# LinuxBoard_v1_1.net
KiCad netlist of a schematic drawn in EAGLE
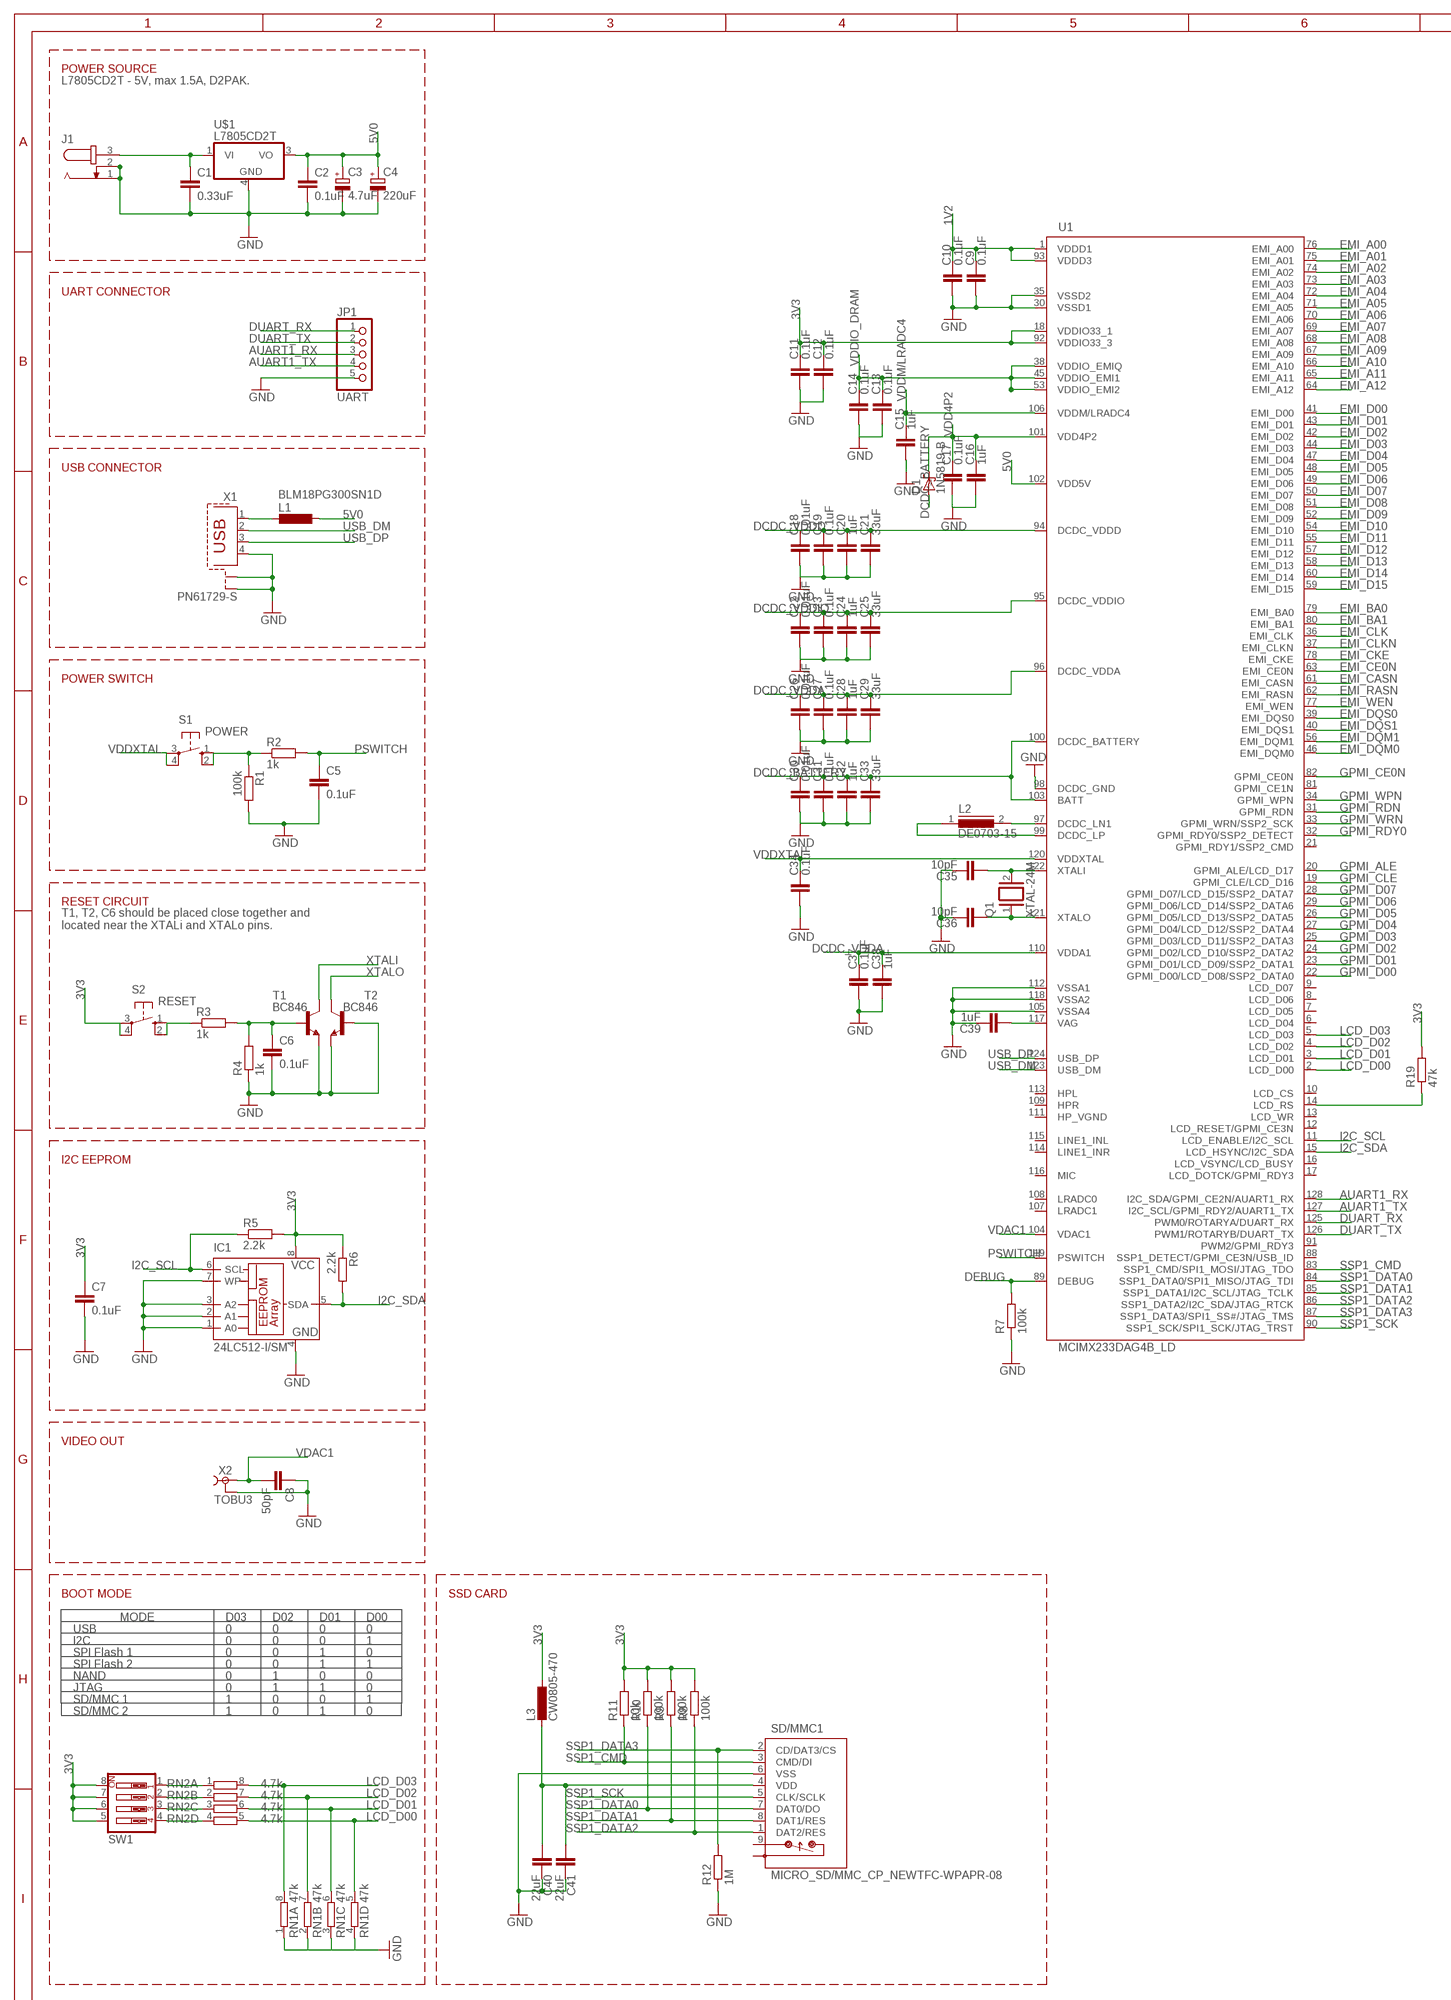
[diagram p0: schematic, sheet 1, part 1 of 2]
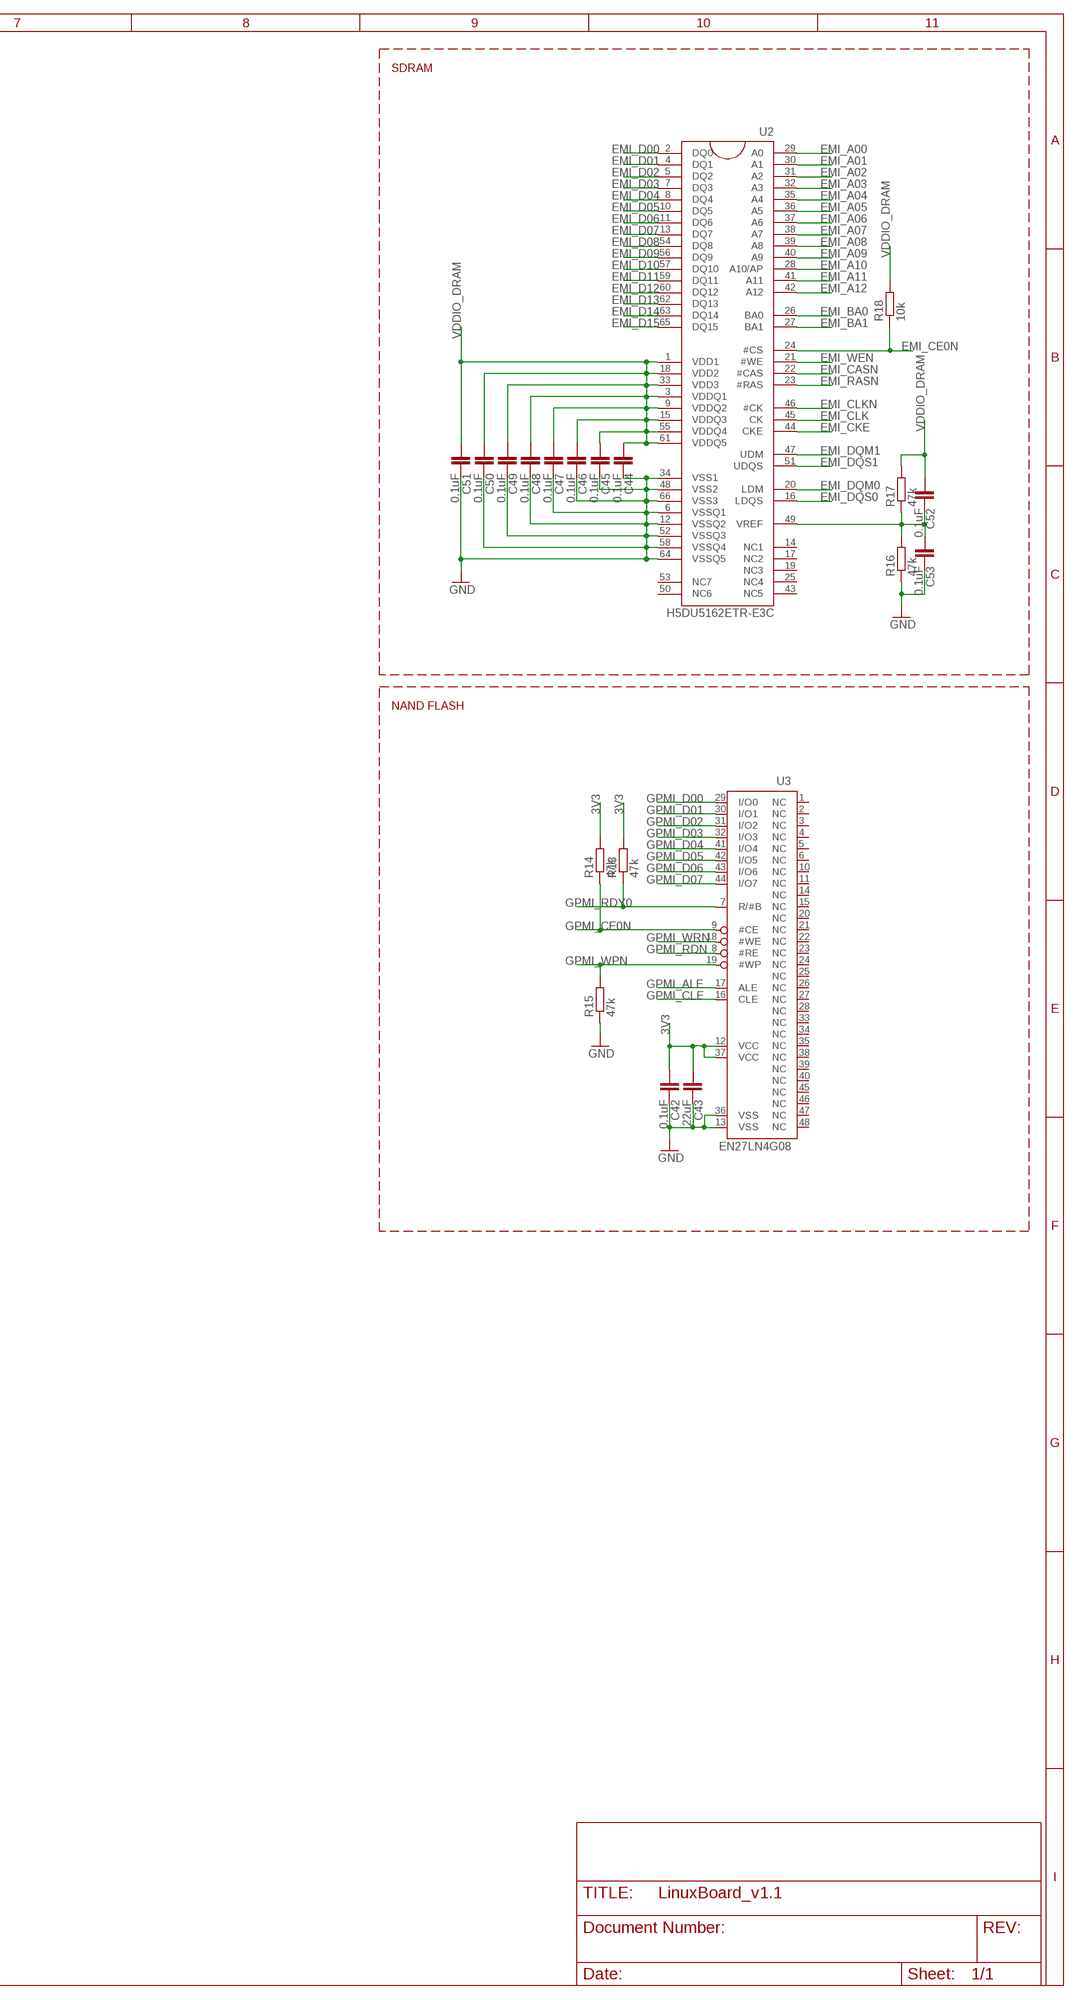
[diagram p1: schematic, sheet 1, part 2 of 2]

(export (version "E")
  (design (tool "Eeschema 10.0.6"))
  (components
    (comp (ref "C1")
      (value "0.33uF")
      (footprint "eagle-import:C0805")
      (libsource (lib "eagle-import") (part "C-EUC0805"))
    )
    (comp (ref "C2")
      (value "0.1uF")
      (footprint "eagle-import:C0805")
      (libsource (lib "eagle-import") (part "C-EUC0805"))
    )
    (comp (ref "C3")
      (value "4.7uF")
      (footprint "eagle-import:E2-5")
      (libsource (lib "eagle-import") (part "CPOL-EUE2-5"))
    )
    (comp (ref "C4")
      (value "220uF")
      (footprint "eagle-import:E2-5")
      (libsource (lib "eagle-import") (part "CPOL-EUE2-5"))
    )
    (comp (ref "C5")
      (value "0.1uF")
      (footprint "eagle-import:C0805")
      (libsource (lib "eagle-import") (part "C-EUC0805"))
    )
    (comp (ref "C6")
      (value "0.1uF")
      (footprint "eagle-import:C0805")
      (libsource (lib "eagle-import") (part "C-EUC0805"))
    )
    (comp (ref "C7")
      (value "0.1uF")
      (footprint "eagle-import:C0805")
      (libsource (lib "eagle-import") (part "C-EUC0805"))
    )
    (comp (ref "C8")
      (value "50pF")
      (footprint "eagle-import:C0805")
      (libsource (lib "eagle-import") (part "C-EUC0805"))
    )
    (comp (ref "C9")
      (value "0.1uF")
      (footprint "eagle-import:C0805")
      (libsource (lib "eagle-import") (part "C-EUC0805"))
    )
    (comp (ref "C10")
      (value "0.1uF")
      (footprint "eagle-import:C0805")
      (libsource (lib "eagle-import") (part "C-EUC0805"))
    )
    (comp (ref "C11")
      (value "0.1uF")
      (footprint "eagle-import:C0805")
      (libsource (lib "eagle-import") (part "C-EUC0805"))
    )
    (comp (ref "C12")
      (value "0.1uF")
      (footprint "eagle-import:C0805")
      (libsource (lib "eagle-import") (part "C-EUC0805"))
    )
    (comp (ref "C13")
      (value "0.1uF")
      (footprint "eagle-import:C0805")
      (libsource (lib "eagle-import") (part "C-EUC0805"))
    )
    (comp (ref "C14")
      (value "0.1uF")
      (footprint "eagle-import:C0805")
      (libsource (lib "eagle-import") (part "C-EUC0805"))
    )
    (comp (ref "C15")
      (value "1uF")
      (footprint "eagle-import:C0805")
      (libsource (lib "eagle-import") (part "C-EUC0805"))
    )
    (comp (ref "C16")
      (value "1uF")
      (footprint "eagle-import:C0805")
      (libsource (lib "eagle-import") (part "C-EUC0805"))
    )
    (comp (ref "C17")
      (value "0.1uF")
      (footprint "eagle-import:C0805")
      (libsource (lib "eagle-import") (part "C-EUC0805"))
    )
    (comp (ref "C18")
      (value "0.01uF")
      (footprint "eagle-import:C0805")
      (libsource (lib "eagle-import") (part "C-EUC0805"))
    )
    (comp (ref "C19")
      (value "0.1uF")
      (footprint "eagle-import:C0805")
      (libsource (lib "eagle-import") (part "C-EUC0805"))
    )
    (comp (ref "C20")
      (value "1uF")
      (footprint "eagle-import:C0805")
      (libsource (lib "eagle-import") (part "C-EUC0805"))
    )
    (comp (ref "C21")
      (value "33uF")
      (footprint "eagle-import:C0805")
      (libsource (lib "eagle-import") (part "C-EUC0805"))
    )
    (comp (ref "C22")
      (value "0.01uF")
      (footprint "eagle-import:C0805")
      (libsource (lib "eagle-import") (part "C-EUC0805"))
    )
    (comp (ref "C23")
      (value "0.1uF")
      (footprint "eagle-import:C0805")
      (libsource (lib "eagle-import") (part "C-EUC0805"))
    )
    (comp (ref "C24")
      (value "1uF")
      (footprint "eagle-import:C0805")
      (libsource (lib "eagle-import") (part "C-EUC0805"))
    )
    (comp (ref "C25")
      (value "33uF")
      (footprint "eagle-import:C0805")
      (libsource (lib "eagle-import") (part "C-EUC0805"))
    )
    (comp (ref "C26")
      (value "0.01uF")
      (footprint "eagle-import:C0805")
      (libsource (lib "eagle-import") (part "C-EUC0805"))
    )
    (comp (ref "C27")
      (value "0.1uF")
      (footprint "eagle-import:C0805")
      (libsource (lib "eagle-import") (part "C-EUC0805"))
    )
    (comp (ref "C28")
      (value "1uF")
      (footprint "eagle-import:C0805")
      (libsource (lib "eagle-import") (part "C-EUC0805"))
    )
    (comp (ref "C29")
      (value "33uF")
      (footprint "eagle-import:C0805")
      (libsource (lib "eagle-import") (part "C-EUC0805"))
    )
    (comp (ref "C30")
      (value "0.01uF")
      (footprint "eagle-import:C0805")
      (libsource (lib "eagle-import") (part "C-EUC0805"))
    )
    (comp (ref "C31")
      (value "0.1uF")
      (footprint "eagle-import:C0805")
      (libsource (lib "eagle-import") (part "C-EUC0805"))
    )
    (comp (ref "C32")
      (value "1uF")
      (footprint "eagle-import:C0805")
      (libsource (lib "eagle-import") (part "C-EUC0805"))
    )
    (comp (ref "C33")
      (value "33uF")
      (footprint "eagle-import:C0805")
      (libsource (lib "eagle-import") (part "C-EUC0805"))
    )
    (comp (ref "C34")
      (value "0.1uF")
      (footprint "eagle-import:C0805")
      (libsource (lib "eagle-import") (part "C-EUC0805"))
    )
    (comp (ref "C35")
      (value "10pF")
      (footprint "eagle-import:C0805")
      (libsource (lib "eagle-import") (part "C-EUC0805"))
    )
    (comp (ref "C36")
      (value "10pF")
      (footprint "eagle-import:C0805")
      (libsource (lib "eagle-import") (part "C-EUC0805"))
    )
    (comp (ref "C37")
      (value "0.1uF")
      (footprint "eagle-import:C0805")
      (libsource (lib "eagle-import") (part "C-EUC0805"))
    )
    (comp (ref "C38")
      (value "1uF")
      (footprint "eagle-import:C0805")
      (libsource (lib "eagle-import") (part "C-EUC0805"))
    )
    (comp (ref "C39")
      (value "1uF")
      (footprint "eagle-import:C0805")
      (libsource (lib "eagle-import") (part "C-EUC0805"))
    )
    (comp (ref "C40")
      (value "22uF")
      (footprint "eagle-import:C0805")
      (libsource (lib "eagle-import") (part "C-EUC0805"))
    )
    (comp (ref "C41")
      (value "22uF")
      (footprint "eagle-import:C0805")
      (libsource (lib "eagle-import") (part "C-EUC0805"))
    )
    (comp (ref "C42")
      (value "0.1uF")
      (footprint "eagle-import:C0805")
      (libsource (lib "eagle-import") (part "C-EUC0805"))
    )
    (comp (ref "C43")
      (value "22uF")
      (footprint "eagle-import:C0805")
      (libsource (lib "eagle-import") (part "C-EUC0805"))
    )
    (comp (ref "C44")
      (value "0.1uF")
      (footprint "eagle-import:C0805")
      (libsource (lib "eagle-import") (part "C-EUC0805"))
    )
    (comp (ref "C45")
      (value "0.1uF")
      (footprint "eagle-import:C0805")
      (libsource (lib "eagle-import") (part "C-EUC0805"))
    )
    (comp (ref "C46")
      (value "0.1uF")
      (footprint "eagle-import:C0805")
      (libsource (lib "eagle-import") (part "C-EUC0805"))
    )
    (comp (ref "C47")
      (value "0.1uF")
      (footprint "eagle-import:C0805")
      (libsource (lib "eagle-import") (part "C-EUC0805"))
    )
    (comp (ref "C48")
      (value "0.1uF")
      (footprint "eagle-import:C0805")
      (libsource (lib "eagle-import") (part "C-EUC0805"))
    )
    (comp (ref "C49")
      (value "0.1uF")
      (footprint "eagle-import:C0805")
      (libsource (lib "eagle-import") (part "C-EUC0805"))
    )
    (comp (ref "C50")
      (value "0.1uF")
      (footprint "eagle-import:C0805")
      (libsource (lib "eagle-import") (part "C-EUC0805"))
    )
    (comp (ref "C51")
      (value "0.1uF")
      (footprint "eagle-import:C0805")
      (libsource (lib "eagle-import") (part "C-EUC0805"))
    )
    (comp (ref "C52")
      (value "0.1uF")
      (footprint "eagle-import:C0805")
      (libsource (lib "eagle-import") (part "C-EUC0805"))
    )
    (comp (ref "C53")
      (value "0.1uF")
      (footprint "eagle-import:C0805")
      (libsource (lib "eagle-import") (part "C-EUC0805"))
    )
    (comp (ref "D1")
      (value "1N5819-B")
      (footprint "eagle-import:DO41-7.6")
      (libsource (lib "eagle-import") (part "1N5819-B"))
    )
    (comp (ref "IC1")
      (value "24LC512-I/SM")
      (footprint "eagle-import:SO-08")
      (fields (field (name "MF") "MICROCHIP") (field (name "MPN") "24LC128-I/SNG"))
      (libsource (lib "eagle-import") (part "24SNLC128"))
    )
    (comp (ref "J1")
      (value "JACK-PLUG0")
      (footprint "eagle-import:SPC4077")
      (libsource (lib "eagle-import") (part "JACK-PLUG0"))
    )
    (comp (ref "JP1")
      (value "UART")
      (footprint "eagle-import:1X05")
      (libsource (lib "eagle-import") (part "PINHD-1X5"))
    )
    (comp (ref "L1")
      (value "BLM18PG300SN1D")
      (footprint "eagle-import:L0201")
      (libsource (lib "eagle-import") (part "L-EUL0201"))
    )
    (comp (ref "L2")
      (value "DE0703-15")
      (footprint "eagle-import:DR73")
      (libsource (lib "eagle-import") (part "DR73"))
    )
    (comp (ref "L3")
      (value "CW0805-470")
      (footprint "eagle-import:L2012C")
      (libsource (lib "eagle-import") (part "L-EUL2012C"))
    )
    (comp (ref "Q1")
      (value "XTAL-24M")
      (footprint "eagle-import:QS")
      (libsource (lib "eagle-import") (part "XTAL/S"))
    )
    (comp (ref "R1")
      (value "100k")
      (footprint "eagle-import:R0805")
      (libsource (lib "eagle-import") (part "R-EU_R0805"))
    )
    (comp (ref "R2")
      (value "1k")
      (footprint "eagle-import:R0805")
      (libsource (lib "eagle-import") (part "R-EU_R0805"))
    )
    (comp (ref "R3")
      (value "1k")
      (footprint "eagle-import:R0805")
      (libsource (lib "eagle-import") (part "R-EU_R0805"))
    )
    (comp (ref "R4")
      (value "1k")
      (footprint "eagle-import:R0805")
      (libsource (lib "eagle-import") (part "R-EU_R0805"))
    )
    (comp (ref "R5")
      (value "2.2k")
      (footprint "eagle-import:R0805")
      (libsource (lib "eagle-import") (part "R-EU_R0805"))
    )
    (comp (ref "R6")
      (value "2.2k")
      (footprint "eagle-import:R0805")
      (libsource (lib "eagle-import") (part "R-EU_R0805"))
    )
    (comp (ref "R7")
      (value "100k")
      (footprint "eagle-import:R0805")
      (libsource (lib "eagle-import") (part "R-EU_R0805"))
    )
    (comp (ref "R8")
      (value "100k")
      (footprint "eagle-import:R0805")
      (libsource (lib "eagle-import") (part "R-EU_R0805"))
    )
    (comp (ref "R9")
      (value "100k")
      (footprint "eagle-import:R0805")
      (libsource (lib "eagle-import") (part "R-EU_R0805"))
    )
    (comp (ref "R10")
      (value "100k")
      (footprint "eagle-import:R0805")
      (libsource (lib "eagle-import") (part "R-EU_R0805"))
    )
    (comp (ref "R11")
      (value "10k")
      (footprint "eagle-import:R0805")
      (libsource (lib "eagle-import") (part "R-EU_R0805"))
    )
    (comp (ref "R12")
      (value "1M")
      (footprint "eagle-import:R0805")
      (libsource (lib "eagle-import") (part "R-EU_R0805"))
    )
    (comp (ref "R13")
      (value "47k")
      (footprint "eagle-import:R0805")
      (libsource (lib "eagle-import") (part "R-EU_R0805"))
    )
    (comp (ref "R14")
      (value "47k")
      (footprint "eagle-import:R0805")
      (libsource (lib "eagle-import") (part "R-EU_R0805"))
    )
    (comp (ref "R15")
      (value "47k")
      (footprint "eagle-import:R0805")
      (libsource (lib "eagle-import") (part "R-EU_R0805"))
    )
    (comp (ref "R16")
      (value "47k")
      (footprint "eagle-import:R0805")
      (libsource (lib "eagle-import") (part "R-EU_R0805"))
    )
    (comp (ref "R17")
      (value "47k")
      (footprint "eagle-import:R0805")
      (libsource (lib "eagle-import") (part "R-EU_R0805"))
    )
    (comp (ref "R18")
      (value "10k")
      (footprint "eagle-import:R0805")
      (libsource (lib "eagle-import") (part "R-EU_R0805"))
    )
    (comp (ref "R19")
      (value "47k")
      (footprint "eagle-import:R0805")
      (libsource (lib "eagle-import") (part "R-EU_R0805"))
    )
    (comp (ref "RN1")
      (value "47k")
      (footprint "eagle-import:YC124")
      (libsource (lib "eagle-import") (part "4R-NYC124"))
    )
    (comp (ref "RN2")
      (value "4.7k")
      (footprint "eagle-import:YC124")
      (libsource (lib "eagle-import") (part "4R-NYC124"))
    )
    (comp (ref "S1")
      (value "POWER")
      (footprint "eagle-import:B3F-10XX")
      (fields (field (name "MPN") "B3F-1000"))
      (libsource (lib "eagle-import") (part "10-XX"))
    )
    (comp (ref "S2")
      (value "RESET")
      (footprint "eagle-import:B3F-10XX")
      (fields (field (name "MPN") "B3F-1000"))
      (libsource (lib "eagle-import") (part "10-XX"))
    )
    (comp (ref "SD/MMC1")
      (value "MICRO_SD/MMC_CP_NEWTFC-WPAPR-08")
      (footprint "eagle-import:TFC-WPAPR-08")
      (libsource (lib "eagle-import") (part "MICRO_SD/MMC_CP_NEWTFC-WPAPR-08"))
    )
    (comp (ref "SW1")
      (value "SW_DIP-4")
      (footprint "eagle-import:EDG-04")
      (libsource (lib "eagle-import") (part "SW_DIP-4"))
    )
    (comp (ref "T1")
      (value "BC846")
      (footprint "eagle-import:SOT23")
      (libsource (lib "eagle-import") (part "BC846"))
    )
    (comp (ref "T2")
      (value "BC846")
      (footprint "eagle-import:SOT23")
      (libsource (lib "eagle-import") (part "BC846"))
    )
    (comp (ref "U$1")
      (value "L7805CD2T")
      (footprint "eagle-import:D2PAK-3")
      (libsource (lib "eagle-import") (part "L7805CD2T"))
    )
    (comp (ref "U1")
      (value "MCIMX233DAG4B_LD")
      (footprint "eagle-import:TQFP128LD")
      (libsource (lib "eagle-import") (part "MCIMX233DAG4B_LD"))
    )
    (comp (ref "U2")
      (value "H5DU5162ETR-E3C")
      (footprint "eagle-import:66TSOP-II")
      (libsource (lib "eagle-import") (part "HY5DU121622D(L)T(P)-J"))
    )
    (comp (ref "U3")
      (value "EN27LN4G08")
      (footprint "eagle-import:TSOP48")
      (libsource (lib "eagle-import") (part "H27UBG8T2A"))
    )
    (comp (ref "X1")
      (value "PN61729-S")
      (footprint "eagle-import:PN61729-S")
      (libsource (lib "eagle-import") (part "PN61729-S"))
    )
    (comp (ref "X2")
      (value "TOBU3")
      (footprint "eagle-import:TOBU3")
      (fields (field (name "MF") "FARNELL") (field (name "MPN") "TOBU 3"))
      (libsource (lib "eagle-import") (part "TOBU3"))
    )
  )
  (nets
    (net (code "1") (name "/1V2") (class "Default")
      (node (ref "C10") (pin "1") (pinfunction "1_1") (pintype "passive"))
      (node (ref "C9") (pin "1") (pinfunction "1_1") (pintype "passive"))
      (node (ref "U1") (pin "1") (pinfunction "VDDD1_1") (pintype "power_in"))
      (node (ref "U1") (pin "93") (pinfunction "VDDD3_93") (pintype "power_in"))
    )
    (net (code "2") (name "/3V3") (class "Default")
      (node (ref "C11") (pin "1") (pinfunction "1_1") (pintype "passive"))
      (node (ref "C12") (pin "1") (pinfunction "1_1") (pintype "passive"))
      (node (ref "C42") (pin "2") (pinfunction "2_2") (pintype "passive"))
      (node (ref "C43") (pin "2") (pinfunction "2_2") (pintype "passive"))
      (node (ref "C7") (pin "1") (pinfunction "1_1") (pintype "passive"))
      (node (ref "IC1") (pin "8") (pinfunction "VCC_8") (pintype "power_in"))
      (node (ref "L3") (pin "1") (pinfunction "1_1") (pintype "passive"))
      (node (ref "R10") (pin "2") (pinfunction "2_2") (pintype "passive"))
      (node (ref "R11") (pin "2") (pinfunction "2_2") (pintype "passive"))
      (node (ref "R13") (pin "2") (pinfunction "2_2") (pintype "passive"))
      (node (ref "R14") (pin "2") (pinfunction "2_2") (pintype "passive"))
      (node (ref "R19") (pin "2") (pinfunction "2_2") (pintype "passive"))
      (node (ref "R5") (pin "2") (pinfunction "2_2") (pintype "passive"))
      (node (ref "R6") (pin "1") (pinfunction "1_1") (pintype "passive"))
      (node (ref "R8") (pin "2") (pinfunction "2_2") (pintype "passive"))
      (node (ref "R9") (pin "2") (pinfunction "2_2") (pintype "passive"))
      (node (ref "S2") (pin "3") (pinfunction "P_3") (pintype "passive"))
      (node (ref "S2") (pin "4") (pinfunction "P1_4") (pintype "passive"))
      (node (ref "SW1") (pin "5") (pinfunction "5_5") (pintype "passive"))
      (node (ref "SW1") (pin "6") (pinfunction "6_6") (pintype "passive"))
      (node (ref "SW1") (pin "7") (pinfunction "7_7") (pintype "passive"))
      (node (ref "SW1") (pin "8") (pinfunction "8_8") (pintype "passive"))
      (node (ref "U1") (pin "18") (pinfunction "VDDIO33_1_18") (pintype "power_in"))
      (node (ref "U1") (pin "92") (pinfunction "VDDIO33_3_92") (pintype "power_in"))
      (node (ref "U3") (pin "12") (pinfunction "VCC_12") (pintype "power_in"))
      (node (ref "U3") (pin "37") (pinfunction "VCC_37") (pintype "power_in"))
    )
    (net (code "3") (name "/5V0") (class "Default")
      (node (ref "C2") (pin "1") (pinfunction "1_1") (pintype "passive"))
      (node (ref "C3") (pin "+") (pinfunction "+_+") (pintype "passive"))
      (node (ref "C4") (pin "+") (pinfunction "+_+") (pintype "passive"))
      (node (ref "L1") (pin "1") (pinfunction "1_1") (pintype "passive"))
      (node (ref "U$1") (pin "3") (pinfunction "VO_3") (pintype "passive"))
      (node (ref "U1") (pin "102") (pinfunction "VDD5V_102") (pintype "power_in"))
    )
    (net (code "4") (name "/AUART1_RX") (class "Default")
      (node (ref "JP1") (pin "3") (pinfunction "3_3") (pintype "passive"))
      (node (ref "U1") (pin "128") (pinfunction "I2C_SDA/GPMI_CE2N/AUART1_RX_128") (pintype "bidirectional"))
    )
    (net (code "5") (name "/AUART1_TX") (class "Default")
      (node (ref "JP1") (pin "4") (pinfunction "4_4") (pintype "passive"))
      (node (ref "U1") (pin "127") (pinfunction "I2C_SCL/GPMI_RDY2/AUART1_TX_127") (pintype "bidirectional"))
    )
    (net (code "6") (name "/DCDC_BATTERY") (class "Default")
      (node (ref "C30") (pin "1") (pinfunction "1_1") (pintype "passive"))
      (node (ref "C31") (pin "1") (pinfunction "1_1") (pintype "passive"))
      (node (ref "C32") (pin "1") (pinfunction "1_1") (pintype "passive"))
      (node (ref "C33") (pin "1") (pinfunction "1_1") (pintype "passive"))
      (node (ref "D1") (pin "A") (pinfunction "A_A") (pintype "passive"))
      (node (ref "U1") (pin "100") (pinfunction "DCDC_BATTERY_100") (pintype "power_in"))
      (node (ref "U1") (pin "103") (pinfunction "BATT_103") (pintype "input"))
    )
    (net (code "7") (name "/DCDC_VDDA") (class "Default")
      (node (ref "C26") (pin "1") (pinfunction "1_1") (pintype "passive"))
      (node (ref "C27") (pin "1") (pinfunction "1_1") (pintype "passive"))
      (node (ref "C28") (pin "1") (pinfunction "1_1") (pintype "passive"))
      (node (ref "C29") (pin "1") (pinfunction "1_1") (pintype "passive"))
      (node (ref "C37") (pin "1") (pinfunction "1_1") (pintype "passive"))
      (node (ref "C38") (pin "1") (pinfunction "1_1") (pintype "passive"))
      (node (ref "U1") (pin "110") (pinfunction "VDDA1_110") (pintype "power_in"))
      (node (ref "U1") (pin "96") (pinfunction "DCDC_VDDA_96") (pintype "power_in"))
    )
    (net (code "8") (name "/DCDC_VDDD") (class "Default")
      (node (ref "C18") (pin "1") (pinfunction "1_1") (pintype "passive"))
      (node (ref "C19") (pin "1") (pinfunction "1_1") (pintype "passive"))
      (node (ref "C20") (pin "1") (pinfunction "1_1") (pintype "passive"))
      (node (ref "C21") (pin "1") (pinfunction "1_1") (pintype "passive"))
      (node (ref "U1") (pin "94") (pinfunction "DCDC_VDDD_94") (pintype "power_in"))
    )
    (net (code "9") (name "/DCDC_VDDIO") (class "Default")
      (node (ref "C22") (pin "1") (pinfunction "1_1") (pintype "passive"))
      (node (ref "C23") (pin "1") (pinfunction "1_1") (pintype "passive"))
      (node (ref "C24") (pin "1") (pinfunction "1_1") (pintype "passive"))
      (node (ref "C25") (pin "1") (pinfunction "1_1") (pintype "passive"))
      (node (ref "U1") (pin "95") (pinfunction "DCDC_VDDIO_95") (pintype "power_in"))
    )
    (net (code "10") (name "/DEBUG") (class "Default")
      (node (ref "R7") (pin "2") (pinfunction "2_2") (pintype "passive"))
      (node (ref "U1") (pin "89") (pinfunction "DEBUG_89") (pintype "bidirectional"))
    )
    (net (code "11") (name "/DUART_RX") (class "Default")
      (node (ref "JP1") (pin "1") (pinfunction "1_1") (pintype "passive"))
      (node (ref "U1") (pin "125") (pinfunction "PWM0/ROTARYA/DUART_RX_125") (pintype "bidirectional"))
    )
    (net (code "12") (name "/DUART_TX") (class "Default")
      (node (ref "JP1") (pin "2") (pinfunction "2_2") (pintype "passive"))
      (node (ref "U1") (pin "126") (pinfunction "PWM1/ROTARYB/DUART_TX_126") (pintype "bidirectional"))
    )
    (net (code "13") (name "/EMI_A00") (class "Default")
      (node (ref "U1") (pin "76") (pinfunction "EMI_A00_76") (pintype "bidirectional"))
      (node (ref "U2") (pin "29") (pinfunction "A0_29") (pintype "input"))
    )
    (net (code "14") (name "/EMI_A01") (class "Default")
      (node (ref "U1") (pin "75") (pinfunction "EMI_A01_75") (pintype "bidirectional"))
      (node (ref "U2") (pin "30") (pinfunction "A1_30") (pintype "input"))
    )
    (net (code "15") (name "/EMI_A02") (class "Default")
      (node (ref "U1") (pin "74") (pinfunction "EMI_A02_74") (pintype "bidirectional"))
      (node (ref "U2") (pin "31") (pinfunction "A2_31") (pintype "input"))
    )
    (net (code "16") (name "/EMI_A03") (class "Default")
      (node (ref "U1") (pin "73") (pinfunction "EMI_A03_73") (pintype "bidirectional"))
      (node (ref "U2") (pin "32") (pinfunction "A3_32") (pintype "input"))
    )
    (net (code "17") (name "/EMI_A04") (class "Default")
      (node (ref "U1") (pin "72") (pinfunction "EMI_A04_72") (pintype "bidirectional"))
      (node (ref "U2") (pin "35") (pinfunction "A4_35") (pintype "input"))
    )
    (net (code "18") (name "/EMI_A05") (class "Default")
      (node (ref "U1") (pin "71") (pinfunction "EMI_A05_71") (pintype "bidirectional"))
      (node (ref "U2") (pin "36") (pinfunction "A5_36") (pintype "input"))
    )
    (net (code "19") (name "/EMI_A06") (class "Default")
      (node (ref "U1") (pin "70") (pinfunction "EMI_A06_70") (pintype "bidirectional"))
      (node (ref "U2") (pin "37") (pinfunction "A6_37") (pintype "input"))
    )
    (net (code "20") (name "/EMI_A07") (class "Default")
      (node (ref "U1") (pin "69") (pinfunction "EMI_A07_69") (pintype "bidirectional"))
      (node (ref "U2") (pin "38") (pinfunction "A7_38") (pintype "input"))
    )
    (net (code "21") (name "/EMI_A08") (class "Default")
      (node (ref "U1") (pin "68") (pinfunction "EMI_A08_68") (pintype "bidirectional"))
      (node (ref "U2") (pin "39") (pinfunction "A8_39") (pintype "input"))
    )
    (net (code "22") (name "/EMI_A09") (class "Default")
      (node (ref "U1") (pin "67") (pinfunction "EMI_A09_67") (pintype "bidirectional"))
      (node (ref "U2") (pin "40") (pinfunction "A9_40") (pintype "input"))
    )
    (net (code "23") (name "/EMI_A10") (class "Default")
      (node (ref "U1") (pin "66") (pinfunction "EMI_A10_66") (pintype "bidirectional"))
      (node (ref "U2") (pin "28") (pinfunction "A10/AP_28") (pintype "input"))
    )
    (net (code "24") (name "/EMI_A11") (class "Default")
      (node (ref "U1") (pin "65") (pinfunction "EMI_A11_65") (pintype "bidirectional"))
      (node (ref "U2") (pin "41") (pinfunction "A11_41") (pintype "input"))
    )
    (net (code "25") (name "/EMI_A12") (class "Default")
      (node (ref "U1") (pin "64") (pinfunction "EMI_A12_64") (pintype "bidirectional"))
      (node (ref "U2") (pin "42") (pinfunction "A12_42") (pintype "input"))
    )
    (net (code "26") (name "/EMI_BA0") (class "Default")
      (node (ref "U1") (pin "79") (pinfunction "EMI_BA0_79") (pintype "output"))
      (node (ref "U2") (pin "26") (pinfunction "BA0_26") (pintype "input"))
    )
    (net (code "27") (name "/EMI_BA1") (class "Default")
      (node (ref "U1") (pin "80") (pinfunction "EMI_BA1_80") (pintype "output"))
      (node (ref "U2") (pin "27") (pinfunction "BA1_27") (pintype "input"))
    )
    (net (code "28") (name "/EMI_CASN") (class "Default")
      (node (ref "U1") (pin "61") (pinfunction "EMI_CASN_61") (pintype "output"))
      (node (ref "U2") (pin "22") (pinfunction "#CAS_22") (pintype "input"))
    )
    (net (code "29") (name "/EMI_CE0N") (class "Default")
      (node (ref "R18") (pin "1") (pinfunction "1_1") (pintype "passive"))
      (node (ref "U1") (pin "63") (pinfunction "EMI_CE0N_63") (pintype "output"))
      (node (ref "U2") (pin "24") (pinfunction "#CS_24") (pintype "input"))
    )
    (net (code "30") (name "/EMI_CKE") (class "Default")
      (node (ref "U1") (pin "78") (pinfunction "EMI_CKE_78") (pintype "output"))
      (node (ref "U2") (pin "44") (pinfunction "CKE_44") (pintype "input"))
    )
    (net (code "31") (name "/EMI_CLK") (class "Default")
      (node (ref "U1") (pin "36") (pinfunction "EMI_CLK_36") (pintype "output"))
      (node (ref "U2") (pin "45") (pinfunction "CK_45") (pintype "input"))
    )
    (net (code "32") (name "/EMI_CLKN") (class "Default")
      (node (ref "U1") (pin "37") (pinfunction "EMI_CLKN_37") (pintype "output"))
      (node (ref "U2") (pin "46") (pinfunction "#CK_46") (pintype "input"))
    )
    (net (code "33") (name "/EMI_D00") (class "Default")
      (node (ref "U1") (pin "41") (pinfunction "EMI_D00_41") (pintype "bidirectional"))
      (node (ref "U2") (pin "2") (pinfunction "DQ0_2") (pintype "bidirectional"))
    )
    (net (code "34") (name "/EMI_D01") (class "Default")
      (node (ref "U1") (pin "43") (pinfunction "EMI_D01_43") (pintype "bidirectional"))
      (node (ref "U2") (pin "4") (pinfunction "DQ1_4") (pintype "bidirectional"))
    )
    (net (code "35") (name "/EMI_D02") (class "Default")
      (node (ref "U1") (pin "42") (pinfunction "EMI_D02_42") (pintype "bidirectional"))
      (node (ref "U2") (pin "5") (pinfunction "DQ2_5") (pintype "bidirectional"))
    )
    (net (code "36") (name "/EMI_D03") (class "Default")
      (node (ref "U1") (pin "44") (pinfunction "EMI_D03_44") (pintype "bidirectional"))
      (node (ref "U2") (pin "7") (pinfunction "DQ3_7") (pintype "bidirectional"))
    )
    (net (code "37") (name "/EMI_D04") (class "Default")
      (node (ref "U1") (pin "47") (pinfunction "EMI_D04_47") (pintype "bidirectional"))
      (node (ref "U2") (pin "8") (pinfunction "DQ4_8") (pintype "bidirectional"))
    )
    (net (code "38") (name "/EMI_D05") (class "Default")
      (node (ref "U1") (pin "48") (pinfunction "EMI_D05_48") (pintype "bidirectional"))
      (node (ref "U2") (pin "10") (pinfunction "DQ5_10") (pintype "bidirectional"))
    )
    (net (code "39") (name "/EMI_D06") (class "Default")
      (node (ref "U1") (pin "49") (pinfunction "EMI_D06_49") (pintype "bidirectional"))
      (node (ref "U2") (pin "11") (pinfunction "DQ6_11") (pintype "bidirectional"))
    )
    (net (code "40") (name "/EMI_D07") (class "Default")
      (node (ref "U1") (pin "50") (pinfunction "EMI_D07_50") (pintype "bidirectional"))
      (node (ref "U2") (pin "13") (pinfunction "DQ7_13") (pintype "bidirectional"))
    )
    (net (code "41") (name "/EMI_D08") (class "Default")
      (node (ref "U1") (pin "51") (pinfunction "EMI_D08_51") (pintype "bidirectional"))
      (node (ref "U2") (pin "54") (pinfunction "DQ8_54") (pintype "bidirectional"))
    )
    (net (code "42") (name "/EMI_D09") (class "Default")
      (node (ref "U1") (pin "52") (pinfunction "EMI_D09_52") (pintype "bidirectional"))
      (node (ref "U2") (pin "56") (pinfunction "DQ9_56") (pintype "bidirectional"))
    )
    (net (code "43") (name "/EMI_D10") (class "Default")
      (node (ref "U1") (pin "54") (pinfunction "EMI_D10_54") (pintype "bidirectional"))
      (node (ref "U2") (pin "57") (pinfunction "DQ10_57") (pintype "bidirectional"))
    )
    (net (code "44") (name "/EMI_D11") (class "Default")
      (node (ref "U1") (pin "55") (pinfunction "EMI_D11_55") (pintype "bidirectional"))
      (node (ref "U2") (pin "59") (pinfunction "DQ11_59") (pintype "bidirectional"))
    )
    (net (code "45") (name "/EMI_D12") (class "Default")
      (node (ref "U1") (pin "57") (pinfunction "EMI_D12_57") (pintype "bidirectional"))
      (node (ref "U2") (pin "60") (pinfunction "DQ12_60") (pintype "bidirectional"))
    )
    (net (code "46") (name "/EMI_D13") (class "Default")
      (node (ref "U1") (pin "58") (pinfunction "EMI_D13_58") (pintype "bidirectional"))
      (node (ref "U2") (pin "62") (pinfunction "DQ13_62") (pintype "bidirectional"))
    )
    (net (code "47") (name "/EMI_D14") (class "Default")
      (node (ref "U1") (pin "60") (pinfunction "EMI_D14_60") (pintype "bidirectional"))
      (node (ref "U2") (pin "63") (pinfunction "DQ14_63") (pintype "bidirectional"))
    )
    (net (code "48") (name "/EMI_D15") (class "Default")
      (node (ref "U1") (pin "59") (pinfunction "EMI_D15_59") (pintype "bidirectional"))
      (node (ref "U2") (pin "65") (pinfunction "DQ15_65") (pintype "bidirectional"))
    )
    (net (code "49") (name "/EMI_DQM0") (class "Default")
      (node (ref "U1") (pin "46") (pinfunction "EMI_DQM0_46") (pintype "output"))
      (node (ref "U2") (pin "20") (pinfunction "LDM_20") (pintype "input"))
    )
    (net (code "50") (name "/EMI_DQM1") (class "Default")
      (node (ref "U1") (pin "56") (pinfunction "EMI_DQM1_56") (pintype "output"))
      (node (ref "U2") (pin "47") (pinfunction "UDM_47") (pintype "input"))
    )
    (net (code "51") (name "/EMI_DQS0") (class "Default")
      (node (ref "U1") (pin "39") (pinfunction "EMI_DQS0_39") (pintype "output"))
      (node (ref "U2") (pin "16") (pinfunction "LDQS_16") (pintype "bidirectional"))
    )
    (net (code "52") (name "/EMI_DQS1") (class "Default")
      (node (ref "U1") (pin "40") (pinfunction "EMI_DQS1_40") (pintype "output"))
      (node (ref "U2") (pin "51") (pinfunction "UDQS_51") (pintype "input"))
    )
    (net (code "53") (name "/EMI_RASN") (class "Default")
      (node (ref "U1") (pin "62") (pinfunction "EMI_RASN_62") (pintype "output"))
      (node (ref "U2") (pin "23") (pinfunction "#RAS_23") (pintype "input"))
    )
    (net (code "54") (name "/EMI_WEN") (class "Default")
      (node (ref "U1") (pin "77") (pinfunction "EMI_WEN_77") (pintype "output"))
      (node (ref "U2") (pin "21") (pinfunction "#WE_21") (pintype "input"))
    )
    (net (code "55") (name "/GPMI_ALE") (class "Default")
      (node (ref "U1") (pin "20") (pinfunction "GPMI_ALE/LCD_D17_20") (pintype "bidirectional"))
      (node (ref "U3") (pin "17") (pinfunction "ALE_17") (pintype "input"))
    )
    (net (code "56") (name "/GPMI_CE0N") (class "Default")
      (node (ref "R14") (pin "1") (pinfunction "1_1") (pintype "passive"))
      (node (ref "U1") (pin "82") (pinfunction "GPMI_CE0N_82") (pintype "bidirectional"))
      (node (ref "U3") (pin "9") (pinfunction "#CE_9") (pintype "input"))
    )
    (net (code "57") (name "/GPMI_CLE") (class "Default")
      (node (ref "U1") (pin "19") (pinfunction "GPMI_CLE/LCD_D16_19") (pintype "bidirectional"))
      (node (ref "U3") (pin "16") (pinfunction "CLE_16") (pintype "input"))
    )
    (net (code "58") (name "/GPMI_D00") (class "Default")
      (node (ref "U1") (pin "22") (pinfunction "GPMI_D00/LCD_D08/SSP2_DATA0_22") (pintype "bidirectional"))
      (node (ref "U3") (pin "29") (pinfunction "I/O0_29") (pintype "bidirectional"))
    )
    (net (code "59") (name "/GPMI_D01") (class "Default")
      (node (ref "U1") (pin "23") (pinfunction "GPMI_D01/LCD_D09/SSP2_DATA1_23") (pintype "bidirectional"))
      (node (ref "U3") (pin "30") (pinfunction "I/O1_30") (pintype "bidirectional"))
    )
    (net (code "60") (name "/GPMI_D02") (class "Default")
      (node (ref "U1") (pin "24") (pinfunction "GPMI_D02/LCD_D10/SSP2_DATA2_24") (pintype "bidirectional"))
      (node (ref "U3") (pin "31") (pinfunction "I/O2_31") (pintype "bidirectional"))
    )
    (net (code "61") (name "/GPMI_D03") (class "Default")
      (node (ref "U1") (pin "25") (pinfunction "GPMI_D03/LCD_D11/SSP2_DATA3_25") (pintype "bidirectional"))
      (node (ref "U3") (pin "32") (pinfunction "I/O3_32") (pintype "bidirectional"))
    )
    (net (code "62") (name "/GPMI_D04") (class "Default")
      (node (ref "U1") (pin "27") (pinfunction "GPMI_D04/LCD_D12/SSP2_DATA4_27") (pintype "bidirectional"))
      (node (ref "U3") (pin "41") (pinfunction "I/O4_41") (pintype "bidirectional"))
    )
    (net (code "63") (name "/GPMI_D05") (class "Default")
      (node (ref "U1") (pin "26") (pinfunction "GPMI_D05/LCD_D13/SSP2_DATA5_26") (pintype "bidirectional"))
      (node (ref "U3") (pin "42") (pinfunction "I/O5_42") (pintype "bidirectional"))
    )
    (net (code "64") (name "/GPMI_D06") (class "Default")
      (node (ref "U1") (pin "29") (pinfunction "GPMI_D06/LCD_D14/SSP2_DATA6_29") (pintype "bidirectional"))
      (node (ref "U3") (pin "43") (pinfunction "I/O6_43") (pintype "bidirectional"))
    )
    (net (code "65") (name "/GPMI_D07") (class "Default")
      (node (ref "U1") (pin "28") (pinfunction "GPMI_D07/LCD_D15/SSP2_DATA7_28") (pintype "bidirectional"))
      (node (ref "U3") (pin "44") (pinfunction "I/O7_44") (pintype "bidirectional"))
    )
    (net (code "66") (name "/GPMI_RDN") (class "Default")
      (node (ref "U1") (pin "31") (pinfunction "GPMI_RDN_31") (pintype "bidirectional"))
      (node (ref "U3") (pin "8") (pinfunction "#RE_8") (pintype "input"))
    )
    (net (code "67") (name "/GPMI_RDY0") (class "Default")
      (node (ref "R13") (pin "1") (pinfunction "1_1") (pintype "passive"))
      (node (ref "U1") (pin "32") (pinfunction "GPMI_RDY0/SSP2_DETECT_32") (pintype "bidirectional"))
      (node (ref "U3") (pin "7") (pinfunction "R/#B_7") (pintype "output"))
    )
    (net (code "68") (name "/GPMI_WPN") (class "Default")
      (node (ref "R15") (pin "2") (pinfunction "2_2") (pintype "passive"))
      (node (ref "U1") (pin "34") (pinfunction "GPMI_WPN_34") (pintype "bidirectional"))
      (node (ref "U3") (pin "19") (pinfunction "#WP_19") (pintype "input"))
    )
    (net (code "69") (name "/GPMI_WRN") (class "Default")
      (node (ref "U1") (pin "33") (pinfunction "GPMI_WRN/SSP2_SCK_33") (pintype "bidirectional"))
      (node (ref "U3") (pin "18") (pinfunction "#WE_18") (pintype "input"))
    )
    (net (code "70") (name "/HP_VGND") (class "Default")
      (node (ref "U1") (pin "111") (pinfunction "HP_VGND_111") (pintype "power_in"))
    )
    (net (code "71") (name "/I2C_SCL") (class "Default")
      (node (ref "IC1") (pin "6") (pinfunction "SCL_6") (pintype "input"))
      (node (ref "R5") (pin "1") (pinfunction "1_1") (pintype "passive"))
      (node (ref "U1") (pin "11") (pinfunction "LCD_ENABLE/I2C_SCL_11") (pintype "bidirectional"))
    )
    (net (code "72") (name "/I2C_SDA") (class "Default")
      (node (ref "IC1") (pin "5") (pinfunction "SDA_5") (pintype "bidirectional"))
      (node (ref "R6") (pin "2") (pinfunction "2_2") (pintype "passive"))
      (node (ref "U1") (pin "15") (pinfunction "LCD_HSYNC/I2C_SDA_15") (pintype "bidirectional"))
    )
    (net (code "73") (name "/LCD_D00") (class "Default")
      (node (ref "RN1") (pin "5") (pinfunction "2_5") (pintype "passive"))
      (node (ref "RN2") (pin "5") (pinfunction "2_5") (pintype "passive"))
      (node (ref "U1") (pin "2") (pinfunction "LCD_D00_2") (pintype "bidirectional"))
    )
    (net (code "74") (name "/LCD_D01") (class "Default")
      (node (ref "RN1") (pin "6") (pinfunction "2_6") (pintype "passive"))
      (node (ref "RN2") (pin "6") (pinfunction "2_6") (pintype "passive"))
      (node (ref "U1") (pin "3") (pinfunction "LCD_D01_3") (pintype "bidirectional"))
    )
    (net (code "75") (name "/LCD_D02") (class "Default")
      (node (ref "RN1") (pin "7") (pinfunction "2_7") (pintype "passive"))
      (node (ref "RN2") (pin "7") (pinfunction "2_7") (pintype "passive"))
      (node (ref "U1") (pin "4") (pinfunction "LCD_D02_4") (pintype "bidirectional"))
    )
    (net (code "76") (name "/LCD_D03") (class "Default")
      (node (ref "RN1") (pin "8") (pinfunction "2_8") (pintype "passive"))
      (node (ref "RN2") (pin "8") (pinfunction "2_8") (pintype "passive"))
      (node (ref "U1") (pin "5") (pinfunction "LCD_D03_5") (pintype "bidirectional"))
    )
    (net (code "77") (name "/PSWITCH") (class "Default")
      (node (ref "C5") (pin "1") (pinfunction "1_1") (pintype "passive"))
      (node (ref "R2") (pin "2") (pinfunction "2_2") (pintype "passive"))
      (node (ref "U1") (pin "119") (pinfunction "PSWITCH_119") (pintype "input"))
    )
    (net (code "78") (name "/SSP1_CMD") (class "Default")
      (node (ref "R11") (pin "1") (pinfunction "1_1") (pintype "passive"))
      (node (ref "SD/MMC1") (pin "3") (pinfunction "CMD/DI_3") (pintype "input"))
      (node (ref "U1") (pin "83") (pinfunction "SSP1_CMD/SPI1_MOSI/JTAG_TDO_83") (pintype "bidirectional"))
    )
    (net (code "79") (name "/SSP1_DATA0") (class "Default")
      (node (ref "R10") (pin "1") (pinfunction "1_1") (pintype "passive"))
      (node (ref "SD/MMC1") (pin "7") (pinfunction "DAT0/DO_7") (pintype "output"))
      (node (ref "U1") (pin "84") (pinfunction "SSP1_DATA0/SPI1_MISO/JTAG_TDI_84") (pintype "bidirectional"))
    )
    (net (code "80") (name "/SSP1_DATA1") (class "Default")
      (node (ref "R9") (pin "1") (pinfunction "1_1") (pintype "passive"))
      (node (ref "SD/MMC1") (pin "8") (pinfunction "DAT1/RES_8") (pintype "bidirectional"))
      (node (ref "U1") (pin "85") (pinfunction "SSP1_DATA1/I2C_SCL/JTAG_TCLK_85") (pintype "bidirectional"))
    )
    (net (code "81") (name "/SSP1_DATA2") (class "Default")
      (node (ref "R8") (pin "1") (pinfunction "1_1") (pintype "passive"))
      (node (ref "SD/MMC1") (pin "1") (pinfunction "DAT2/RES_1") (pintype "bidirectional"))
      (node (ref "U1") (pin "86") (pinfunction "SSP1_DATA2/I2C_SDA/JTAG_RTCK_86") (pintype "bidirectional"))
    )
    (net (code "82") (name "/SSP1_DATA3") (class "Default")
      (node (ref "R12") (pin "2") (pinfunction "2_2") (pintype "passive"))
      (node (ref "SD/MMC1") (pin "2") (pinfunction "CD/DAT3/CS_2") (pintype "input"))
      (node (ref "U1") (pin "87") (pinfunction "SSP1_DATA3/SPI1_SS#/JTAG_TMS_87") (pintype "bidirectional"))
    )
    (net (code "83") (name "/SSP1_SCK") (class "Default")
      (node (ref "SD/MMC1") (pin "5") (pinfunction "CLK/SCLK_5") (pintype "input"))
      (node (ref "U1") (pin "90") (pinfunction "SSP1_SCK/SPI1_SCK/JTAG_TRST_90") (pintype "bidirectional"))
    )
    (net (code "84") (name "/USB_DM") (class "Default")
      (node (ref "U1") (pin "123") (pinfunction "USB_DM_123") (pintype "bidirectional"))
      (node (ref "X1") (pin "2") (pinfunction "2_2") (pintype "passive"))
    )
    (net (code "85") (name "/USB_DP") (class "Default")
      (node (ref "U1") (pin "124") (pinfunction "USB_DP_124") (pintype "bidirectional"))
      (node (ref "X1") (pin "3") (pinfunction "3_3") (pintype "passive"))
    )
    (net (code "86") (name "/VDAC1") (class "Default")
      (node (ref "C8") (pin "2") (pinfunction "2_2") (pintype "passive"))
      (node (ref "U1") (pin "104") (pinfunction "VDAC1_104") (pintype "output"))
      (node (ref "X2") (pin "1") (pinfunction "1_1") (pintype "passive"))
    )
    (net (code "87") (name "/VDD4P2") (class "Default")
      (node (ref "C16") (pin "1") (pinfunction "1_1") (pintype "passive"))
      (node (ref "C17") (pin "1") (pinfunction "1_1") (pintype "passive"))
      (node (ref "D1") (pin "C") (pinfunction "C_C") (pintype "passive"))
      (node (ref "U1") (pin "101") (pinfunction "VDD4P2_101") (pintype "power_in"))
    )
    (net (code "88") (name "/VDDIO_DRAM") (class "Default")
      (node (ref "C13") (pin "1") (pinfunction "1_1") (pintype "passive"))
      (node (ref "C14") (pin "1") (pinfunction "1_1") (pintype "passive"))
      (node (ref "C44") (pin "2") (pinfunction "2_2") (pintype "passive"))
      (node (ref "C45") (pin "2") (pinfunction "2_2") (pintype "passive"))
      (node (ref "C46") (pin "2") (pinfunction "2_2") (pintype "passive"))
      (node (ref "C47") (pin "2") (pinfunction "2_2") (pintype "passive"))
      (node (ref "C48") (pin "2") (pinfunction "2_2") (pintype "passive"))
      (node (ref "C49") (pin "2") (pinfunction "2_2") (pintype "passive"))
      (node (ref "C50") (pin "2") (pinfunction "2_2") (pintype "passive"))
      (node (ref "C51") (pin "2") (pinfunction "2_2") (pintype "passive"))
      (node (ref "C52") (pin "2") (pinfunction "2_2") (pintype "passive"))
      (node (ref "R17") (pin "2") (pinfunction "2_2") (pintype "passive"))
      (node (ref "R18") (pin "2") (pinfunction "2_2") (pintype "passive"))
      (node (ref "U1") (pin "38") (pinfunction "VDDIO_EMIQ_38") (pintype "power_in"))
      (node (ref "U1") (pin "45") (pinfunction "VDDIO_EMI1_45") (pintype "power_in"))
      (node (ref "U1") (pin "53") (pinfunction "VDDIO_EMI2_53") (pintype "power_in"))
      (node (ref "U2") (pin "1") (pinfunction "VDD1_1") (pintype "power_in"))
      (node (ref "U2") (pin "15") (pinfunction "VDDQ3_15") (pintype "power_in"))
      (node (ref "U2") (pin "18") (pinfunction "VDD2_18") (pintype "power_in"))
      (node (ref "U2") (pin "3") (pinfunction "VDDQ1_3") (pintype "power_in"))
      (node (ref "U2") (pin "33") (pinfunction "VDD3_33") (pintype "power_in"))
      (node (ref "U2") (pin "55") (pinfunction "VDDQ4_55") (pintype "power_in"))
      (node (ref "U2") (pin "61") (pinfunction "VDDQ5_61") (pintype "power_in"))
      (node (ref "U2") (pin "9") (pinfunction "VDDQ2_9") (pintype "power_in"))
    )
    (net (code "89") (name "/VDDM{slash}LRADC4") (class "Default")
      (node (ref "C15") (pin "1") (pinfunction "1_1") (pintype "passive"))
      (node (ref "U1") (pin "106") (pinfunction "VDDM/LRADC4_106") (pintype "power_in"))
    )
    (net (code "90") (name "/VDDXTAL") (class "Default")
      (node (ref "C34") (pin "1") (pinfunction "1_1") (pintype "passive"))
      (node (ref "S1") (pin "3") (pinfunction "P_3") (pintype "passive"))
      (node (ref "S1") (pin "4") (pinfunction "P1_4") (pintype "passive"))
      (node (ref "U1") (pin "120") (pinfunction "VDDXTAL_120") (pintype "passive"))
    )
    (net (code "91") (name "/XTALI") (class "Default")
      (node (ref "C35") (pin "2") (pinfunction "2_2") (pintype "passive"))
      (node (ref "Q1") (pin "2") (pinfunction "2_2") (pintype "passive"))
      (node (ref "T1") (pin "3") (pinfunction "C_3") (pintype "passive"))
      (node (ref "U1") (pin "122") (pinfunction "XTALI_122") (pintype "input"))
    )
    (net (code "92") (name "/XTALO") (class "Default")
      (node (ref "C36") (pin "2") (pinfunction "2_2") (pintype "passive"))
      (node (ref "Q1") (pin "1") (pinfunction "1_1") (pintype "passive"))
      (node (ref "T2") (pin "3") (pinfunction "C_3") (pintype "passive"))
      (node (ref "U1") (pin "121") (pinfunction "XTALO_121") (pintype "output"))
    )
    (net (code "93") (name "GND") (class "Default")
      (node (ref "C1") (pin "2") (pinfunction "2_2") (pintype "passive"))
      (node (ref "C10") (pin "2") (pinfunction "2_2") (pintype "passive"))
      (node (ref "C11") (pin "2") (pinfunction "2_2") (pintype "passive"))
      (node (ref "C12") (pin "2") (pinfunction "2_2") (pintype "passive"))
      (node (ref "C13") (pin "2") (pinfunction "2_2") (pintype "passive"))
      (node (ref "C14") (pin "2") (pinfunction "2_2") (pintype "passive"))
      (node (ref "C15") (pin "2") (pinfunction "2_2") (pintype "passive"))
      (node (ref "C16") (pin "2") (pinfunction "2_2") (pintype "passive"))
      (node (ref "C17") (pin "2") (pinfunction "2_2") (pintype "passive"))
      (node (ref "C18") (pin "2") (pinfunction "2_2") (pintype "passive"))
      (node (ref "C19") (pin "2") (pinfunction "2_2") (pintype "passive"))
      (node (ref "C2") (pin "2") (pinfunction "2_2") (pintype "passive"))
      (node (ref "C20") (pin "2") (pinfunction "2_2") (pintype "passive"))
      (node (ref "C21") (pin "2") (pinfunction "2_2") (pintype "passive"))
      (node (ref "C22") (pin "2") (pinfunction "2_2") (pintype "passive"))
      (node (ref "C23") (pin "2") (pinfunction "2_2") (pintype "passive"))
      (node (ref "C24") (pin "2") (pinfunction "2_2") (pintype "passive"))
      (node (ref "C25") (pin "2") (pinfunction "2_2") (pintype "passive"))
      (node (ref "C26") (pin "2") (pinfunction "2_2") (pintype "passive"))
      (node (ref "C27") (pin "2") (pinfunction "2_2") (pintype "passive"))
      (node (ref "C28") (pin "2") (pinfunction "2_2") (pintype "passive"))
      (node (ref "C29") (pin "2") (pinfunction "2_2") (pintype "passive"))
      (node (ref "C3") (pin "-") (pinfunction "-_-") (pintype "passive"))
      (node (ref "C30") (pin "2") (pinfunction "2_2") (pintype "passive"))
      (node (ref "C31") (pin "2") (pinfunction "2_2") (pintype "passive"))
      (node (ref "C32") (pin "2") (pinfunction "2_2") (pintype "passive"))
      (node (ref "C33") (pin "2") (pinfunction "2_2") (pintype "passive"))
      (node (ref "C34") (pin "2") (pinfunction "2_2") (pintype "passive"))
      (node (ref "C35") (pin "1") (pinfunction "1_1") (pintype "passive"))
      (node (ref "C36") (pin "1") (pinfunction "1_1") (pintype "passive"))
      (node (ref "C37") (pin "2") (pinfunction "2_2") (pintype "passive"))
      (node (ref "C38") (pin "2") (pinfunction "2_2") (pintype "passive"))
      (node (ref "C39") (pin "1") (pinfunction "1_1") (pintype "passive"))
      (node (ref "C4") (pin "-") (pinfunction "-_-") (pintype "passive"))
      (node (ref "C40") (pin "1") (pinfunction "1_1") (pintype "passive"))
      (node (ref "C41") (pin "1") (pinfunction "1_1") (pintype "passive"))
      (node (ref "C42") (pin "1") (pinfunction "1_1") (pintype "passive"))
      (node (ref "C43") (pin "1") (pinfunction "1_1") (pintype "passive"))
      (node (ref "C44") (pin "1") (pinfunction "1_1") (pintype "passive"))
      (node (ref "C45") (pin "1") (pinfunction "1_1") (pintype "passive"))
      (node (ref "C46") (pin "1") (pinfunction "1_1") (pintype "passive"))
      (node (ref "C47") (pin "1") (pinfunction "1_1") (pintype "passive"))
      (node (ref "C48") (pin "1") (pinfunction "1_1") (pintype "passive"))
      (node (ref "C49") (pin "1") (pinfunction "1_1") (pintype "passive"))
      (node (ref "C5") (pin "2") (pinfunction "2_2") (pintype "passive"))
      (node (ref "C50") (pin "1") (pinfunction "1_1") (pintype "passive"))
      (node (ref "C51") (pin "1") (pinfunction "1_1") (pintype "passive"))
      (node (ref "C53") (pin "1") (pinfunction "1_1") (pintype "passive"))
      (node (ref "C6") (pin "2") (pinfunction "2_2") (pintype "passive"))
      (node (ref "C7") (pin "2") (pinfunction "2_2") (pintype "passive"))
      (node (ref "C8") (pin "1") (pinfunction "1_1") (pintype "passive"))
      (node (ref "C9") (pin "2") (pinfunction "2_2") (pintype "passive"))
      (node (ref "IC1") (pin "1") (pinfunction "A0_1") (pintype "input"))
      (node (ref "IC1") (pin "2") (pinfunction "A1_2") (pintype "input"))
      (node (ref "IC1") (pin "3") (pinfunction "A2_3") (pintype "input"))
      (node (ref "IC1") (pin "4") (pinfunction "GND_4") (pintype "power_in"))
      (node (ref "IC1") (pin "7") (pinfunction "WP_7") (pintype "input"))
      (node (ref "J1") (pin "1") (pinfunction "1_1") (pintype "passive"))
      (node (ref "J1") (pin "2") (pinfunction "2_2") (pintype "passive"))
      (node (ref "JP1") (pin "5") (pinfunction "5_5") (pintype "passive"))
      (node (ref "R1") (pin "2") (pinfunction "2_2") (pintype "passive"))
      (node (ref "R12") (pin "1") (pinfunction "1_1") (pintype "passive"))
      (node (ref "R15") (pin "1") (pinfunction "1_1") (pintype "passive"))
      (node (ref "R16") (pin "1") (pinfunction "1_1") (pintype "passive"))
      (node (ref "R4") (pin "1") (pinfunction "1_1") (pintype "passive"))
      (node (ref "R7") (pin "1") (pinfunction "1_1") (pintype "passive"))
      (node (ref "RN1") (pin "1") (pinfunction "1_1") (pintype "passive"))
      (node (ref "RN1") (pin "2") (pinfunction "1_2") (pintype "passive"))
      (node (ref "RN1") (pin "3") (pinfunction "1_3") (pintype "passive"))
      (node (ref "RN1") (pin "4") (pinfunction "1_4") (pintype "passive"))
      (node (ref "SD/MMC1") (pin "6") (pinfunction "VSS_6") (pintype "power_in"))
      (node (ref "T1") (pin "2") (pinfunction "E_2") (pintype "passive"))
      (node (ref "T2") (pin "1") (pinfunction "B_1") (pintype "passive"))
      (node (ref "T2") (pin "2") (pinfunction "E_2") (pintype "passive"))
      (node (ref "U$1") (pin "4") (pinfunction "GND_4") (pintype "passive"))
      (node (ref "U1") (pin "105") (pinfunction "VSSA4_105") (pintype "power_in"))
      (node (ref "U1") (pin "112") (pinfunction "VSSA1_112") (pintype "power_in"))
      (node (ref "U1") (pin "118") (pinfunction "VSSA2_118") (pintype "power_in"))
      (node (ref "U1") (pin "30") (pinfunction "VSSD1_30") (pintype "power_in"))
      (node (ref "U1") (pin "35") (pinfunction "VSSD2_35") (pintype "power_in"))
      (node (ref "U1") (pin "98") (pinfunction "DCDC_GND_98") (pintype "power_in"))
      (node (ref "U2") (pin "12") (pinfunction "VSSQ2_12") (pintype "power_in"))
      (node (ref "U2") (pin "34") (pinfunction "VSS1_34") (pintype "power_in"))
      (node (ref "U2") (pin "48") (pinfunction "VSS2_48") (pintype "power_in"))
      (node (ref "U2") (pin "52") (pinfunction "VSSQ3_52") (pintype "power_in"))
      (node (ref "U2") (pin "58") (pinfunction "VSSQ4_58") (pintype "power_in"))
      (node (ref "U2") (pin "6") (pinfunction "VSSQ1_6") (pintype "power_in"))
      (node (ref "U2") (pin "64") (pinfunction "VSSQ5_64") (pintype "power_in"))
      (node (ref "U2") (pin "66") (pinfunction "VSS3_66") (pintype "power_in"))
      (node (ref "U3") (pin "13") (pinfunction "VSS_13") (pintype "power_in"))
      (node (ref "U3") (pin "36") (pinfunction "VSS_36") (pintype "power_in"))
      (node (ref "X1") (pin "4") (pinfunction "4_4") (pintype "passive"))
      (node (ref "X1") (pin "S1") (pinfunction "S1_S1") (pintype "passive"))
      (node (ref "X1") (pin "S2") (pinfunction "S2_S2") (pintype "passive"))
      (node (ref "X2") (pin "2") (pinfunction "2_2") (pintype "passive"))
      (node (ref "X2") (pin "2@1") (pinfunction "2_2@1") (pintype "passive"))
      (node (ref "X2") (pin "2@2") (pinfunction "2_2@2") (pintype "passive"))
    )
    (net (code "94") (name "Net-(L1-Pad2)") (class "Default")
      (node (ref "L1") (pin "2") (pinfunction "2_2") (pintype "passive"))
      (node (ref "X1") (pin "1") (pinfunction "1_1") (pintype "passive"))
    )
    (net (code "95") (name "Net-(RN2-Pad1)") (class "Default")
      (node (ref "RN2") (pin "1") (pinfunction "1_1") (pintype "passive"))
      (node (ref "SW1") (pin "1") (pinfunction "1_1") (pintype "passive"))
    )
    (net (code "96") (name "Net-(RN2B-1)") (class "Default")
      (node (ref "RN2") (pin "2") (pinfunction "1_2") (pintype "passive"))
      (node (ref "SW1") (pin "2") (pinfunction "2_2") (pintype "passive"))
    )
    (net (code "97") (name "Net-(RN2C-1)") (class "Default")
      (node (ref "RN2") (pin "3") (pinfunction "1_3") (pintype "passive"))
      (node (ref "SW1") (pin "3") (pinfunction "3_3") (pintype "passive"))
    )
    (net (code "98") (name "Net-(RN2D-1)") (class "Default")
      (node (ref "RN2") (pin "4") (pinfunction "1_4") (pintype "passive"))
      (node (ref "SW1") (pin "4") (pinfunction "4_4") (pintype "passive"))
    )
    (net (code "99") (name "Net-(S1-S)") (class "Default")
      (node (ref "R1") (pin "1") (pinfunction "1_1") (pintype "passive"))
      (node (ref "R2") (pin "1") (pinfunction "1_1") (pintype "passive"))
      (node (ref "S1") (pin "1") (pinfunction "S_1") (pintype "passive"))
      (node (ref "S1") (pin "2") (pinfunction "S1_2") (pintype "passive"))
    )
    (net (code "100") (name "Net-(S2-S)") (class "Default")
      (node (ref "R3") (pin "1") (pinfunction "1_1") (pintype "passive"))
      (node (ref "S2") (pin "1") (pinfunction "S_1") (pintype "passive"))
      (node (ref "S2") (pin "2") (pinfunction "S1_2") (pintype "passive"))
    )
    (net (code "101") (name "Net-(SD/MMC1-VDD)") (class "Default")
      (node (ref "C40") (pin "2") (pinfunction "2_2") (pintype "passive"))
      (node (ref "C41") (pin "2") (pinfunction "2_2") (pintype "passive"))
      (node (ref "L3") (pin "2") (pinfunction "2_2") (pintype "passive"))
      (node (ref "SD/MMC1") (pin "4") (pinfunction "VDD_4") (pintype "power_in"))
    )
    (net (code "102") (name "Net-(T1-B)") (class "Default")
      (node (ref "C6") (pin "1") (pinfunction "1_1") (pintype "passive"))
      (node (ref "R3") (pin "2") (pinfunction "2_2") (pintype "passive"))
      (node (ref "R4") (pin "2") (pinfunction "2_2") (pintype "passive"))
      (node (ref "T1") (pin "1") (pinfunction "B_1") (pintype "passive"))
    )
    (net (code "103") (name "Net-(U$1-VI)") (class "Default")
      (node (ref "C1") (pin "1") (pinfunction "1_1") (pintype "passive"))
      (node (ref "J1") (pin "3") (pinfunction "3_3") (pintype "passive"))
      (node (ref "U$1") (pin "1") (pinfunction "VI_1") (pintype "input"))
    )
    (net (code "104") (name "Net-(U1-DCDC_LN1)") (class "Default")
      (node (ref "L2") (pin "2") (pinfunction "2_2") (pintype "passive"))
      (node (ref "U1") (pin "97") (pinfunction "DCDC_LN1_97") (pintype "passive"))
    )
    (net (code "105") (name "Net-(U1-DCDC_LP)") (class "Default")
      (node (ref "L2") (pin "1") (pinfunction "1_1") (pintype "passive"))
      (node (ref "U1") (pin "99") (pinfunction "DCDC_LP_99") (pintype "passive"))
    )
    (net (code "106") (name "Net-(U1-LCD_RS)") (class "Default")
      (node (ref "R19") (pin "1") (pinfunction "1_1") (pintype "passive"))
      (node (ref "U1") (pin "14") (pinfunction "LCD_RS_14") (pintype "bidirectional"))
    )
    (net (code "107") (name "Net-(U1-VAG)") (class "Default")
      (node (ref "C39") (pin "2") (pinfunction "2_2") (pintype "passive"))
      (node (ref "U1") (pin "117") (pinfunction "VAG_117") (pintype "passive"))
    )
    (net (code "108") (name "Net-(U2-VREF)") (class "Default")
      (node (ref "C52") (pin "1") (pinfunction "1_1") (pintype "passive"))
      (node (ref "C53") (pin "2") (pinfunction "2_2") (pintype "passive"))
      (node (ref "R16") (pin "2") (pinfunction "2_2") (pintype "passive"))
      (node (ref "R17") (pin "1") (pinfunction "1_1") (pintype "passive"))
      (node (ref "U2") (pin "49") (pinfunction "VREF_49") (pintype "input"))
    )
    (net (code "109") (name "unconnected-(SD/MMC1-CP_E-Pad9)") (class "Default")
      (node (ref "SD/MMC1") (pin "9") (pinfunction "CP_E_9") (pintype "input"))
    )
    (net (code "110") (name "unconnected-(SD/MMC1-PACK1-Pad10)") (class "Default")
      (node (ref "SD/MMC1") (pin "10") (pinfunction "PACK1_10") (pintype "input"))
    )
    (net (code "111") (name "unconnected-(U1-GPMI_CE1N-Pad81)") (class "Default")
      (node (ref "U1") (pin "81") (pinfunction "GPMI_CE1N_81") (pintype "bidirectional"))
    )
    (net (code "112") (name "unconnected-(U1-GPMI_RDY1{slash}SSP2_CMD-Pad21)") (class "Default")
      (node (ref "U1") (pin "21") (pinfunction "GPMI_RDY1/SSP2_CMD_21") (pintype "bidirectional"))
    )
    (net (code "113") (name "unconnected-(U1-HPL-Pad113)") (class "Default")
      (node (ref "U1") (pin "113") (pinfunction "HPL_113") (pintype "output"))
    )
    (net (code "114") (name "unconnected-(U1-HPR-Pad109)") (class "Default")
      (node (ref "U1") (pin "109") (pinfunction "HPR_109") (pintype "output"))
    )
    (net (code "115") (name "unconnected-(U1-LCD_CS-Pad10)") (class "Default")
      (node (ref "U1") (pin "10") (pinfunction "LCD_CS_10") (pintype "bidirectional"))
    )
    (net (code "116") (name "unconnected-(U1-LCD_D04-Pad6)") (class "Default")
      (node (ref "U1") (pin "6") (pinfunction "LCD_D04_6") (pintype "bidirectional"))
    )
    (net (code "117") (name "unconnected-(U1-LCD_D05-Pad7)") (class "Default")
      (node (ref "U1") (pin "7") (pinfunction "LCD_D05_7") (pintype "bidirectional"))
    )
    (net (code "118") (name "unconnected-(U1-LCD_D06-Pad8)") (class "Default")
      (node (ref "U1") (pin "8") (pinfunction "LCD_D06_8") (pintype "bidirectional"))
    )
    (net (code "119") (name "unconnected-(U1-LCD_D07-Pad9)") (class "Default")
      (node (ref "U1") (pin "9") (pinfunction "LCD_D07_9") (pintype "bidirectional"))
    )
    (net (code "120") (name "unconnected-(U1-LCD_DOTCK{slash}GPMI_RDY3-Pad17)") (class "Default")
      (node (ref "U1") (pin "17") (pinfunction "LCD_DOTCK/GPMI_RDY3_17") (pintype "bidirectional"))
    )
    (net (code "121") (name "unconnected-(U1-LCD_RESET{slash}GPMI_CE3N-Pad12)") (class "Default")
      (node (ref "U1") (pin "12") (pinfunction "LCD_RESET/GPMI_CE3N_12") (pintype "bidirectional"))
    )
    (net (code "122") (name "unconnected-(U1-LCD_VSYNC{slash}LCD_BUSY-Pad16)") (class "Default")
      (node (ref "U1") (pin "16") (pinfunction "LCD_VSYNC/LCD_BUSY_16") (pintype "bidirectional"))
    )
    (net (code "123") (name "unconnected-(U1-LCD_WR-Pad13)") (class "Default")
      (node (ref "U1") (pin "13") (pinfunction "LCD_WR_13") (pintype "bidirectional"))
    )
    (net (code "124") (name "unconnected-(U1-LINE1_INL-Pad115)") (class "Default")
      (node (ref "U1") (pin "115") (pinfunction "LINE1_INL_115") (pintype "input"))
    )
    (net (code "125") (name "unconnected-(U1-LINE1_INR-Pad114)") (class "Default")
      (node (ref "U1") (pin "114") (pinfunction "LINE1_INR_114") (pintype "input"))
    )
    (net (code "126") (name "unconnected-(U1-LRADC0-Pad108)") (class "Default")
      (node (ref "U1") (pin "108") (pinfunction "LRADC0_108") (pintype "bidirectional"))
    )
    (net (code "127") (name "unconnected-(U1-LRADC1-Pad107)") (class "Default")
      (node (ref "U1") (pin "107") (pinfunction "LRADC1_107") (pintype "bidirectional"))
    )
    (net (code "128") (name "unconnected-(U1-MIC-Pad116)") (class "Default")
      (node (ref "U1") (pin "116") (pinfunction "MIC_116") (pintype "input"))
    )
    (net (code "129") (name "unconnected-(U1-PWM2{slash}GPMI_RDY3-Pad91)") (class "Default")
      (node (ref "U1") (pin "91") (pinfunction "PWM2/GPMI_RDY3_91") (pintype "bidirectional"))
    )
    (net (code "130") (name "unconnected-(U1-SSP1_DETECT{slash}GPMI_CE3N{slash}USB_ID-Pad88)") (class "Default")
      (node (ref "U1") (pin "88") (pinfunction "SSP1_DETECT/GPMI_CE3N/USB_ID_88") (pintype "bidirectional"))
    )
    (net (code "131") (name "unconnected-(U2-NC1-Pad14)") (class "Default")
      (node (ref "U2") (pin "14") (pinfunction "NC1_14") (pintype "no_connect"))
    )
    (net (code "132") (name "unconnected-(U2-NC2-Pad17)") (class "Default")
      (node (ref "U2") (pin "17") (pinfunction "NC2_17") (pintype "no_connect"))
    )
    (net (code "133") (name "unconnected-(U2-NC3-Pad19)") (class "Default")
      (node (ref "U2") (pin "19") (pinfunction "NC3_19") (pintype "no_connect"))
    )
    (net (code "134") (name "unconnected-(U2-NC4-Pad25)") (class "Default")
      (node (ref "U2") (pin "25") (pinfunction "NC4_25") (pintype "no_connect"))
    )
    (net (code "135") (name "unconnected-(U2-NC5-Pad43)") (class "Default")
      (node (ref "U2") (pin "43") (pinfunction "NC5_43") (pintype "no_connect"))
    )
    (net (code "136") (name "unconnected-(U2-NC6-Pad50)") (class "Default")
      (node (ref "U2") (pin "50") (pinfunction "NC6_50") (pintype "no_connect"))
    )
    (net (code "137") (name "unconnected-(U2-NC7-Pad53)") (class "Default")
      (node (ref "U2") (pin "53") (pinfunction "NC7_53") (pintype "no_connect"))
    )
    (net (code "138") (name "unconnected-(U3-NC-Pad1)") (class "Default")
      (node (ref "U3") (pin "1") (pinfunction "NC_1") (pintype "no_connect"))
    )
    (net (code "139") (name "unconnected-(U3-NC-Pad2)") (class "Default")
      (node (ref "U3") (pin "2") (pinfunction "NC_2") (pintype "no_connect"))
    )
    (net (code "140") (name "unconnected-(U3-NC-Pad3)") (class "Default")
      (node (ref "U3") (pin "3") (pinfunction "NC_3") (pintype "no_connect"))
    )
    (net (code "141") (name "unconnected-(U3-NC-Pad4)") (class "Default")
      (node (ref "U3") (pin "4") (pinfunction "NC_4") (pintype "no_connect"))
    )
    (net (code "142") (name "unconnected-(U3-NC-Pad5)") (class "Default")
      (node (ref "U3") (pin "5") (pinfunction "NC_5") (pintype "no_connect"))
    )
    (net (code "143") (name "unconnected-(U3-NC-Pad6)") (class "Default")
      (node (ref "U3") (pin "6") (pinfunction "NC_6") (pintype "no_connect"))
    )
    (net (code "144") (name "unconnected-(U3-NC-Pad10)") (class "Default")
      (node (ref "U3") (pin "10") (pinfunction "NC_10") (pintype "no_connect"))
    )
    (net (code "145") (name "unconnected-(U3-NC-Pad11)") (class "Default")
      (node (ref "U3") (pin "11") (pinfunction "NC_11") (pintype "no_connect"))
    )
    (net (code "146") (name "unconnected-(U3-NC-Pad14)") (class "Default")
      (node (ref "U3") (pin "14") (pinfunction "NC_14") (pintype "no_connect"))
    )
    (net (code "147") (name "unconnected-(U3-NC-Pad15)") (class "Default")
      (node (ref "U3") (pin "15") (pinfunction "NC_15") (pintype "no_connect"))
    )
    (net (code "148") (name "unconnected-(U3-NC-Pad20)") (class "Default")
      (node (ref "U3") (pin "20") (pinfunction "NC_20") (pintype "no_connect"))
    )
    (net (code "149") (name "unconnected-(U3-NC-Pad21)") (class "Default")
      (node (ref "U3") (pin "21") (pinfunction "NC_21") (pintype "no_connect"))
    )
    (net (code "150") (name "unconnected-(U3-NC-Pad22)") (class "Default")
      (node (ref "U3") (pin "22") (pinfunction "NC_22") (pintype "no_connect"))
    )
    (net (code "151") (name "unconnected-(U3-NC-Pad23)") (class "Default")
      (node (ref "U3") (pin "23") (pinfunction "NC_23") (pintype "no_connect"))
    )
    (net (code "152") (name "unconnected-(U3-NC-Pad24)") (class "Default")
      (node (ref "U3") (pin "24") (pinfunction "NC_24") (pintype "no_connect"))
    )
    (net (code "153") (name "unconnected-(U3-NC-Pad25)") (class "Default")
      (node (ref "U3") (pin "25") (pinfunction "NC_25") (pintype "no_connect"))
    )
    (net (code "154") (name "unconnected-(U3-NC-Pad26)") (class "Default")
      (node (ref "U3") (pin "26") (pinfunction "NC_26") (pintype "no_connect"))
    )
    (net (code "155") (name "unconnected-(U3-NC-Pad27)") (class "Default")
      (node (ref "U3") (pin "27") (pinfunction "NC_27") (pintype "no_connect"))
    )
    (net (code "156") (name "unconnected-(U3-NC-Pad28)") (class "Default")
      (node (ref "U3") (pin "28") (pinfunction "NC_28") (pintype "no_connect"))
    )
    (net (code "157") (name "unconnected-(U3-NC-Pad33)") (class "Default")
      (node (ref "U3") (pin "33") (pinfunction "NC_33") (pintype "no_connect"))
    )
    (net (code "158") (name "unconnected-(U3-NC-Pad34)") (class "Default")
      (node (ref "U3") (pin "34") (pinfunction "NC_34") (pintype "no_connect"))
    )
    (net (code "159") (name "unconnected-(U3-NC-Pad35)") (class "Default")
      (node (ref "U3") (pin "35") (pinfunction "NC_35") (pintype "no_connect"))
    )
    (net (code "160") (name "unconnected-(U3-NC-Pad38)") (class "Default")
      (node (ref "U3") (pin "38") (pinfunction "NC_38") (pintype "no_connect"))
    )
    (net (code "161") (name "unconnected-(U3-NC-Pad39)") (class "Default")
      (node (ref "U3") (pin "39") (pinfunction "NC_39") (pintype "no_connect"))
    )
    (net (code "162") (name "unconnected-(U3-NC-Pad40)") (class "Default")
      (node (ref "U3") (pin "40") (pinfunction "NC_40") (pintype "no_connect"))
    )
    (net (code "163") (name "unconnected-(U3-NC-Pad45)") (class "Default")
      (node (ref "U3") (pin "45") (pinfunction "NC_45") (pintype "no_connect"))
    )
    (net (code "164") (name "unconnected-(U3-NC-Pad46)") (class "Default")
      (node (ref "U3") (pin "46") (pinfunction "NC_46") (pintype "no_connect"))
    )
    (net (code "165") (name "unconnected-(U3-NC-Pad47)") (class "Default")
      (node (ref "U3") (pin "47") (pinfunction "NC_47") (pintype "no_connect"))
    )
    (net (code "166") (name "unconnected-(U3-NC-Pad48)") (class "Default")
      (node (ref "U3") (pin "48") (pinfunction "NC_48") (pintype "no_connect"))
    )
  )
)
